# TurboMaster-clean_noart.net
KiCad netlist of a schematic drawn in EAGLE
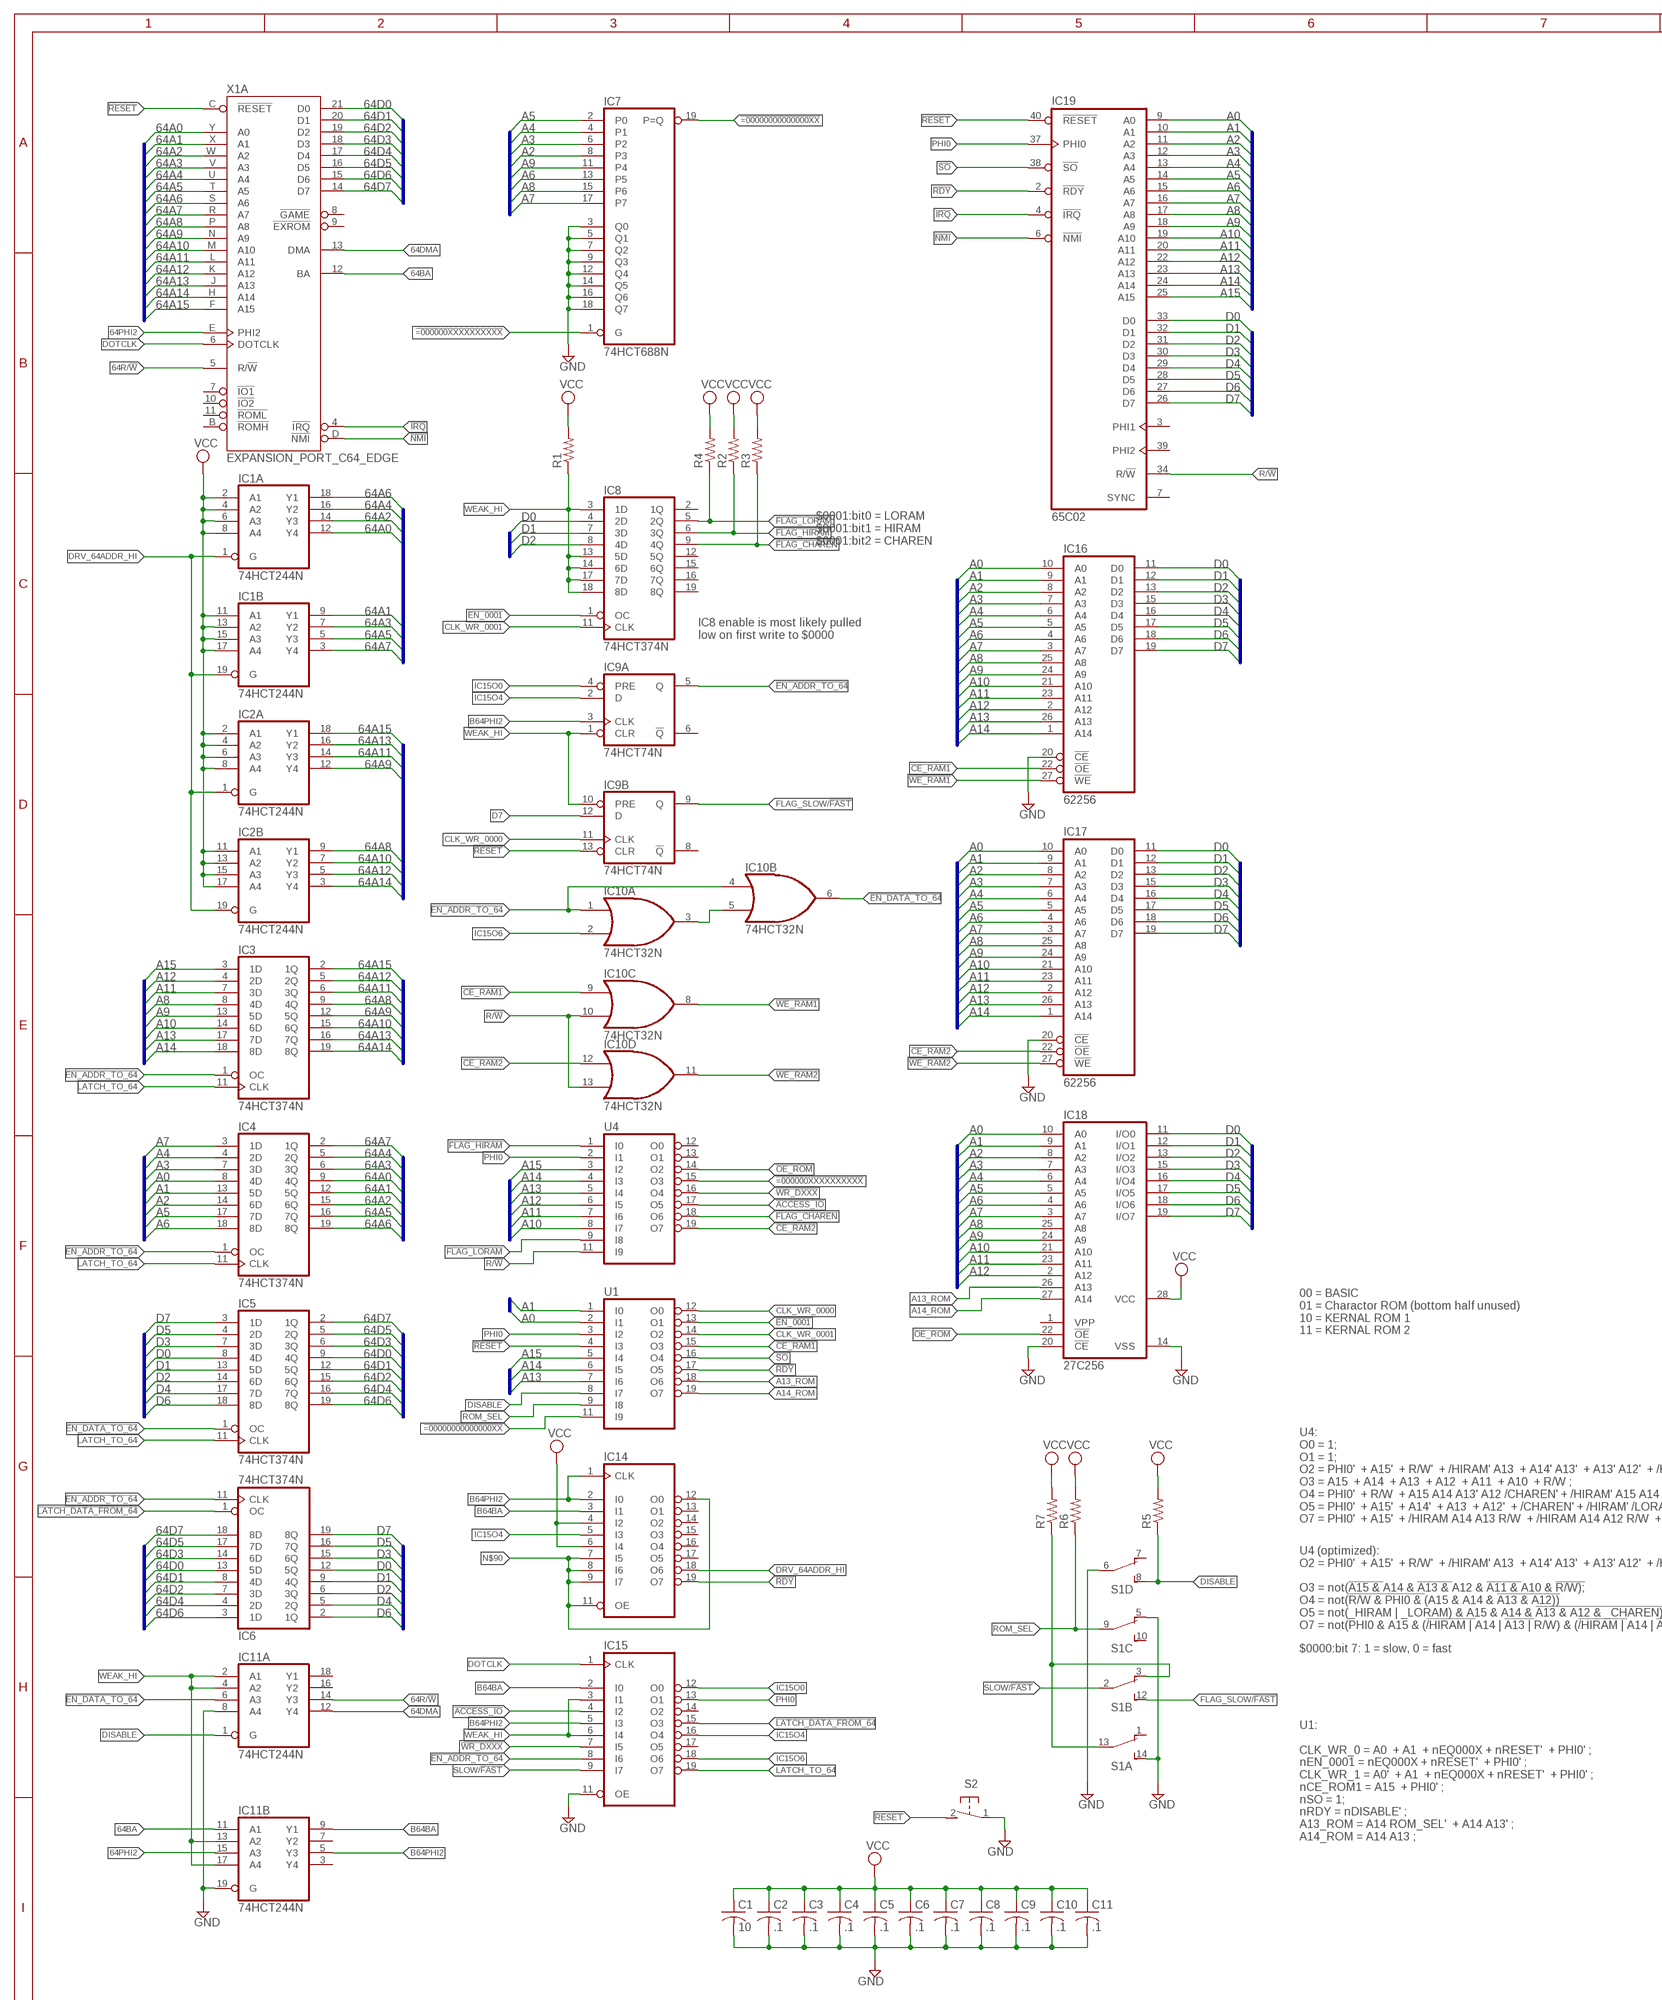
[diagram p0: schematic, sheet 1, part 1 of 2]
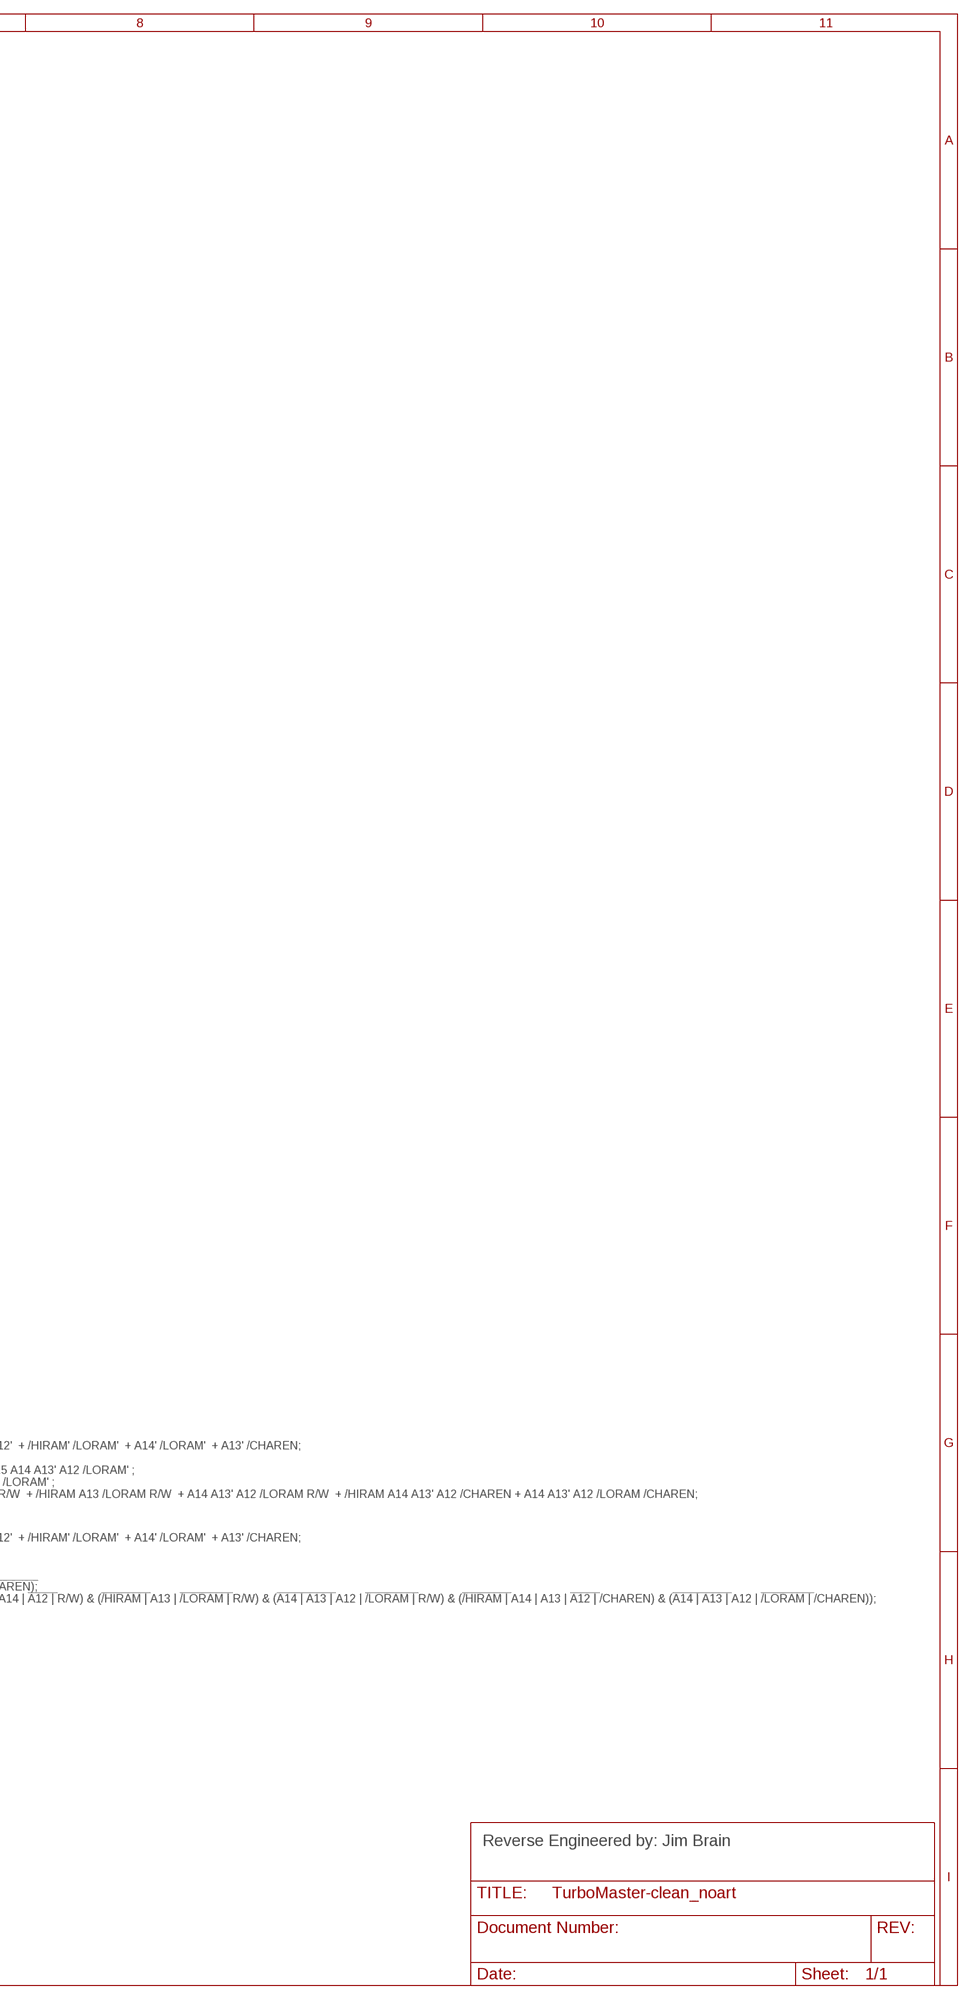
[diagram p1: schematic, sheet 1, part 2 of 2]

(export (version "E")
  (design (tool "Eeschema 10.0.6"))
  (components
    (comp (ref "C1")
      (value "10")
      (footprint "eagle-import:C050-024X044")
      (libsource (lib "eagle-import") (part "C-US050-024X044"))
    )
    (comp (ref "C2")
      (value ".1")
      (footprint "eagle-import:C050-024X044")
      (libsource (lib "eagle-import") (part "C-US050-024X044"))
    )
    (comp (ref "C3")
      (value ".1")
      (footprint "eagle-import:C050-024X044")
      (libsource (lib "eagle-import") (part "C-US050-024X044"))
    )
    (comp (ref "C4")
      (value ".1")
      (footprint "eagle-import:C050-024X044")
      (libsource (lib "eagle-import") (part "C-US050-024X044"))
    )
    (comp (ref "C5")
      (value ".1")
      (footprint "eagle-import:C050-024X044")
      (libsource (lib "eagle-import") (part "C-US050-024X044"))
    )
    (comp (ref "C6")
      (value ".1")
      (footprint "eagle-import:C050-024X044")
      (libsource (lib "eagle-import") (part "C-US050-024X044"))
    )
    (comp (ref "C7")
      (value ".1")
      (footprint "eagle-import:C050-024X044")
      (libsource (lib "eagle-import") (part "C-US050-024X044"))
    )
    (comp (ref "C8")
      (value ".1")
      (footprint "eagle-import:C050-024X044")
      (libsource (lib "eagle-import") (part "C-US050-024X044"))
    )
    (comp (ref "C9")
      (value ".1")
      (footprint "eagle-import:C050-024X044")
      (libsource (lib "eagle-import") (part "C-US050-024X044"))
    )
    (comp (ref "C10")
      (value ".1")
      (footprint "eagle-import:C050-024X044")
      (libsource (lib "eagle-import") (part "C-US050-024X044"))
    )
    (comp (ref "C11")
      (value ".1")
      (footprint "eagle-import:C050-024X044")
      (libsource (lib "eagle-import") (part "C-US050-024X044"))
    )
    (comp (ref "IC1")
      (value "74HCT244N")
      (footprint "eagle-import:DIL20-RP")
      (libsource (lib "eagle-import") (part "74244NHCT"))
    )
    (comp (ref "IC2")
      (value "74HCT244N")
      (footprint "eagle-import:DIL20-RP")
      (libsource (lib "eagle-import") (part "74244NHCT"))
    )
    (comp (ref "IC3")
      (value "74HCT374N")
      (footprint "eagle-import:DIL20-RP")
      (libsource (lib "eagle-import") (part "74374NHCT"))
    )
    (comp (ref "IC4")
      (value "74HCT374N")
      (footprint "eagle-import:DIL20-RP")
      (libsource (lib "eagle-import") (part "74374NHCT"))
    )
    (comp (ref "IC5")
      (value "74HCT374N")
      (footprint "eagle-import:DIL20-RP")
      (libsource (lib "eagle-import") (part "74374NHCT"))
    )
    (comp (ref "IC6")
      (value "74HCT374N")
      (footprint "eagle-import:DIL20-RP")
      (libsource (lib "eagle-import") (part "74374NHCT"))
    )
    (comp (ref "IC7")
      (value "74HCT688N")
      (footprint "eagle-import:DIL20-RP")
      (libsource (lib "eagle-import") (part "74688NHCT"))
    )
    (comp (ref "IC8")
      (value "74HCT374N")
      (footprint "eagle-import:DIL20-RP")
      (libsource (lib "eagle-import") (part "74374NHCT"))
    )
    (comp (ref "IC9")
      (value "74HCT74N")
      (footprint "eagle-import:DIL14-RP")
      (libsource (lib "eagle-import") (part "7474NHCT"))
    )
    (comp (ref "IC10")
      (value "74HCT32N")
      (footprint "eagle-import:DIL14-RP")
      (libsource (lib "eagle-import") (part "7432NHCT"))
    )
    (comp (ref "IC11")
      (value "74HCT244N")
      (footprint "eagle-import:DIL20-RP")
      (libsource (lib "eagle-import") (part "74244NHCT"))
    )
    (comp (ref "IC14")
      (value "16R4-RP")
      (footprint "eagle-import:DIL20-RP")
      (libsource (lib "eagle-import") (part "16R4-RP"))
    )
    (comp (ref "IC15")
      (value "16R6-RP")
      (footprint "eagle-import:DIL20-RP")
      (libsource (lib "eagle-import") (part "16R6-RP"))
    )
    (comp (ref "IC16")
      (value "62256")
      (footprint "eagle-import:DIL28-6-RP")
      (libsource (lib "eagle-import") (part "JEDEC_32KB_SRAM-RP"))
    )
    (comp (ref "IC17")
      (value "62256")
      (footprint "eagle-import:DIL28-6-RP")
      (libsource (lib "eagle-import") (part "JEDEC_32KB_SRAM-RP"))
    )
    (comp (ref "IC18")
      (value "27C256")
      (footprint "eagle-import:DIL28-6-RP")
      (libsource (lib "eagle-import") (part "27C256AG-RP"))
    )
    (comp (ref "IC19")
      (value "65C02")
      (footprint "eagle-import:DIL40-ROUNDPAD")
      (libsource (lib "eagle-import") (part "6502-RPC"))
    )
    (comp (ref "R1")
      (value "R-US_0207/10")
      (footprint "eagle-import:0207_10")
      (libsource (lib "eagle-import") (part "R-US_0207/10"))
    )
    (comp (ref "R2")
      (value "R-US_0207/10")
      (footprint "eagle-import:0207_10")
      (libsource (lib "eagle-import") (part "R-US_0207/10"))
    )
    (comp (ref "R3")
      (value "R-US_0207/10")
      (footprint "eagle-import:0207_10")
      (libsource (lib "eagle-import") (part "R-US_0207/10"))
    )
    (comp (ref "R4")
      (value "R-US_0207/10")
      (footprint "eagle-import:0207_10")
      (libsource (lib "eagle-import") (part "R-US_0207/10"))
    )
    (comp (ref "R5")
      (value "R-US_0207/10")
      (footprint "eagle-import:0207_10")
      (libsource (lib "eagle-import") (part "R-US_0207/10"))
    )
    (comp (ref "R6")
      (value "R-US_0207/10")
      (footprint "eagle-import:0207_10")
      (libsource (lib "eagle-import") (part "R-US_0207/10"))
    )
    (comp (ref "R7")
      (value "R-US_0207/10")
      (footprint "eagle-import:0207_10")
      (libsource (lib "eagle-import") (part "R-US_0207/10"))
    )
    (comp (ref "S1")
      (value "DIP04DPDTS-RP")
      (footprint "eagle-import:DIP04DPDTS-RP")
      (libsource (lib "eagle-import") (part "DIP04DPDTS-RP"))
    )
    (comp (ref "S2")
      (value "31-XX")
      (footprint "eagle-import:B3F-31XX")
      (fields (field (name "MPN") "B3F-3100"))
      (libsource (lib "eagle-import") (part "31-XX"))
    )
    (comp (ref "U1")
      (value "16L8-RP")
      (footprint "eagle-import:DIL20-RP")
      (libsource (lib "eagle-import") (part "16L8-RP"))
    )
    (comp (ref "U4")
      (value "16L8-RP")
      (footprint "eagle-import:DIL20-RP")
      (libsource (lib "eagle-import") (part "16L8-RP"))
    )
    (comp (ref "X1")
      (value "EXPANSION_PORT_C64_EDGE")
      (footprint "eagle-import:MA100-22-2")
      (libsource (lib "eagle-import") (part "EXPANSION_PORT_C64_EDGE"))
    )
  )
  (nets
    (net (code "1") (name "/64A0") (class "Default")
      (node (ref "IC1") (pin "12") (pinfunction "Y4_12") (pintype "tri_state"))
      (node (ref "IC4") (pin "9") (pinfunction "4Q_9") (pintype "tri_state"))
      (node (ref "X1") (pin "Y") (pinfunction "A0_Y") (pintype "bidirectional"))
    )
    (net (code "2") (name "/64A1") (class "Default")
      (node (ref "IC1") (pin "9") (pinfunction "Y1_9") (pintype "tri_state"))
      (node (ref "IC4") (pin "12") (pinfunction "5Q_12") (pintype "tri_state"))
      (node (ref "X1") (pin "X") (pinfunction "A1_X") (pintype "bidirectional"))
    )
    (net (code "3") (name "/64A2") (class "Default")
      (node (ref "IC1") (pin "14") (pinfunction "Y3_14") (pintype "tri_state"))
      (node (ref "IC4") (pin "15") (pinfunction "6Q_15") (pintype "tri_state"))
      (node (ref "X1") (pin "W") (pinfunction "A2_W") (pintype "bidirectional"))
    )
    (net (code "4") (name "/64A3") (class "Default")
      (node (ref "IC1") (pin "7") (pinfunction "Y2_7") (pintype "tri_state"))
      (node (ref "IC4") (pin "6") (pinfunction "3Q_6") (pintype "tri_state"))
      (node (ref "X1") (pin "V") (pinfunction "A3_V") (pintype "bidirectional"))
    )
    (net (code "5") (name "/64A4") (class "Default")
      (node (ref "IC1") (pin "16") (pinfunction "Y2_16") (pintype "tri_state"))
      (node (ref "IC4") (pin "5") (pinfunction "2Q_5") (pintype "tri_state"))
      (node (ref "X1") (pin "U") (pinfunction "A4_U") (pintype "bidirectional"))
    )
    (net (code "6") (name "/64A5") (class "Default")
      (node (ref "IC1") (pin "5") (pinfunction "Y3_5") (pintype "tri_state"))
      (node (ref "IC4") (pin "16") (pinfunction "7Q_16") (pintype "tri_state"))
      (node (ref "X1") (pin "T") (pinfunction "A5_T") (pintype "bidirectional"))
    )
    (net (code "7") (name "/64A6") (class "Default")
      (node (ref "IC1") (pin "18") (pinfunction "Y1_18") (pintype "tri_state"))
      (node (ref "IC4") (pin "19") (pinfunction "8Q_19") (pintype "tri_state"))
      (node (ref "X1") (pin "S") (pinfunction "A6_S") (pintype "bidirectional"))
    )
    (net (code "8") (name "/64A7") (class "Default")
      (node (ref "IC1") (pin "3") (pinfunction "Y4_3") (pintype "tri_state"))
      (node (ref "IC4") (pin "2") (pinfunction "1Q_2") (pintype "tri_state"))
      (node (ref "X1") (pin "R") (pinfunction "A7_R") (pintype "bidirectional"))
    )
    (net (code "9") (name "/64A8") (class "Default")
      (node (ref "IC2") (pin "9") (pinfunction "Y1_9") (pintype "tri_state"))
      (node (ref "IC3") (pin "9") (pinfunction "4Q_9") (pintype "tri_state"))
      (node (ref "X1") (pin "P") (pinfunction "A8_P") (pintype "bidirectional"))
    )
    (net (code "10") (name "/64A9") (class "Default")
      (node (ref "IC2") (pin "12") (pinfunction "Y4_12") (pintype "tri_state"))
      (node (ref "IC3") (pin "12") (pinfunction "5Q_12") (pintype "tri_state"))
      (node (ref "X1") (pin "N") (pinfunction "A9_N") (pintype "bidirectional"))
    )
    (net (code "11") (name "/64A10") (class "Default")
      (node (ref "IC2") (pin "7") (pinfunction "Y2_7") (pintype "tri_state"))
      (node (ref "IC3") (pin "15") (pinfunction "6Q_15") (pintype "tri_state"))
      (node (ref "X1") (pin "M") (pinfunction "A10_M") (pintype "bidirectional"))
    )
    (net (code "12") (name "/64A11") (class "Default")
      (node (ref "IC2") (pin "14") (pinfunction "Y3_14") (pintype "tri_state"))
      (node (ref "IC3") (pin "6") (pinfunction "3Q_6") (pintype "tri_state"))
      (node (ref "X1") (pin "L") (pinfunction "A11_L") (pintype "bidirectional"))
    )
    (net (code "13") (name "/64A12") (class "Default")
      (node (ref "IC2") (pin "5") (pinfunction "Y3_5") (pintype "tri_state"))
      (node (ref "IC3") (pin "5") (pinfunction "2Q_5") (pintype "tri_state"))
      (node (ref "X1") (pin "K") (pinfunction "A12_K") (pintype "bidirectional"))
    )
    (net (code "14") (name "/64A13") (class "Default")
      (node (ref "IC2") (pin "16") (pinfunction "Y2_16") (pintype "tri_state"))
      (node (ref "IC3") (pin "16") (pinfunction "7Q_16") (pintype "tri_state"))
      (node (ref "X1") (pin "J") (pinfunction "A13_J") (pintype "bidirectional"))
    )
    (net (code "15") (name "/64A14") (class "Default")
      (node (ref "IC2") (pin "3") (pinfunction "Y4_3") (pintype "tri_state"))
      (node (ref "IC3") (pin "19") (pinfunction "8Q_19") (pintype "tri_state"))
      (node (ref "X1") (pin "H") (pinfunction "A14_H") (pintype "bidirectional"))
    )
    (net (code "16") (name "/64A15") (class "Default")
      (node (ref "IC2") (pin "18") (pinfunction "Y1_18") (pintype "tri_state"))
      (node (ref "IC3") (pin "2") (pinfunction "1Q_2") (pintype "tri_state"))
      (node (ref "X1") (pin "F") (pinfunction "A15_F") (pintype "bidirectional"))
    )
    (net (code "17") (name "/64D0") (class "Default")
      (node (ref "IC5") (pin "9") (pinfunction "4Q_9") (pintype "tri_state"))
      (node (ref "IC6") (pin "13") (pinfunction "5D_13") (pintype "input"))
      (node (ref "X1") (pin "21") (pinfunction "D0_21") (pintype "bidirectional"))
    )
    (net (code "18") (name "/64D1") (class "Default")
      (node (ref "IC5") (pin "12") (pinfunction "5Q_12") (pintype "tri_state"))
      (node (ref "IC6") (pin "8") (pinfunction "4D_8") (pintype "input"))
      (node (ref "X1") (pin "20") (pinfunction "D1_20") (pintype "bidirectional"))
    )
    (net (code "19") (name "/64D2") (class "Default")
      (node (ref "IC5") (pin "15") (pinfunction "6Q_15") (pintype "tri_state"))
      (node (ref "IC6") (pin "7") (pinfunction "3D_7") (pintype "input"))
      (node (ref "X1") (pin "19") (pinfunction "D2_19") (pintype "bidirectional"))
    )
    (net (code "20") (name "/64D3") (class "Default")
      (node (ref "IC5") (pin "6") (pinfunction "3Q_6") (pintype "tri_state"))
      (node (ref "IC6") (pin "14") (pinfunction "6D_14") (pintype "input"))
      (node (ref "X1") (pin "18") (pinfunction "D3_18") (pintype "bidirectional"))
    )
    (net (code "21") (name "/64D4") (class "Default")
      (node (ref "IC5") (pin "16") (pinfunction "7Q_16") (pintype "tri_state"))
      (node (ref "IC6") (pin "4") (pinfunction "2D_4") (pintype "input"))
      (node (ref "X1") (pin "17") (pinfunction "D4_17") (pintype "bidirectional"))
    )
    (net (code "22") (name "/64D5") (class "Default")
      (node (ref "IC5") (pin "5") (pinfunction "2Q_5") (pintype "tri_state"))
      (node (ref "IC6") (pin "17") (pinfunction "7D_17") (pintype "input"))
      (node (ref "X1") (pin "16") (pinfunction "D5_16") (pintype "bidirectional"))
    )
    (net (code "23") (name "/64D6") (class "Default")
      (node (ref "IC5") (pin "19") (pinfunction "8Q_19") (pintype "tri_state"))
      (node (ref "IC6") (pin "3") (pinfunction "1D_3") (pintype "input"))
      (node (ref "X1") (pin "15") (pinfunction "D6_15") (pintype "bidirectional"))
    )
    (net (code "24") (name "/64D7") (class "Default")
      (node (ref "IC5") (pin "2") (pinfunction "1Q_2") (pintype "tri_state"))
      (node (ref "IC6") (pin "18") (pinfunction "8D_18") (pintype "input"))
      (node (ref "X1") (pin "14") (pinfunction "D7_14") (pintype "bidirectional"))
    )
    (net (code "25") (name "/64R{slash}~{W}") (class "Default")
      (node (ref "IC11") (pin "14") (pinfunction "Y3_14") (pintype "tri_state"))
      (node (ref "X1") (pin "5") (pinfunction "R/~{W}_5") (pintype "bidirectional"))
    )
    (net (code "26") (name "/A0") (class "Default")
      (node (ref "IC16") (pin "10") (pinfunction "A0_10") (pintype "input"))
      (node (ref "IC17") (pin "10") (pinfunction "A0_10") (pintype "input"))
      (node (ref "IC18") (pin "10") (pinfunction "A0_10") (pintype "input"))
      (node (ref "IC19") (pin "9") (pinfunction "A0_9") (pintype "output"))
      (node (ref "IC4") (pin "8") (pinfunction "4D_8") (pintype "input"))
      (node (ref "U1") (pin "2") (pinfunction "I1_2") (pintype "input"))
    )
    (net (code "27") (name "/A1") (class "Default")
      (node (ref "IC16") (pin "9") (pinfunction "A1_9") (pintype "input"))
      (node (ref "IC17") (pin "9") (pinfunction "A1_9") (pintype "input"))
      (node (ref "IC18") (pin "9") (pinfunction "A1_9") (pintype "input"))
      (node (ref "IC19") (pin "10") (pinfunction "A1_10") (pintype "output"))
      (node (ref "IC4") (pin "13") (pinfunction "5D_13") (pintype "input"))
      (node (ref "U1") (pin "1") (pinfunction "I0_1") (pintype "input"))
    )
    (net (code "28") (name "/A2") (class "Default")
      (node (ref "IC16") (pin "8") (pinfunction "A2_8") (pintype "input"))
      (node (ref "IC17") (pin "8") (pinfunction "A2_8") (pintype "input"))
      (node (ref "IC18") (pin "8") (pinfunction "A2_8") (pintype "input"))
      (node (ref "IC19") (pin "11") (pinfunction "A2_11") (pintype "output"))
      (node (ref "IC4") (pin "14") (pinfunction "6D_14") (pintype "input"))
      (node (ref "IC7") (pin "8") (pinfunction "P3_8") (pintype "input"))
    )
    (net (code "29") (name "/A3") (class "Default")
      (node (ref "IC16") (pin "7") (pinfunction "A3_7") (pintype "input"))
      (node (ref "IC17") (pin "7") (pinfunction "A3_7") (pintype "input"))
      (node (ref "IC18") (pin "7") (pinfunction "A3_7") (pintype "input"))
      (node (ref "IC19") (pin "12") (pinfunction "A3_12") (pintype "output"))
      (node (ref "IC4") (pin "7") (pinfunction "3D_7") (pintype "input"))
      (node (ref "IC7") (pin "6") (pinfunction "P2_6") (pintype "input"))
    )
    (net (code "30") (name "/A4") (class "Default")
      (node (ref "IC16") (pin "6") (pinfunction "A4_6") (pintype "input"))
      (node (ref "IC17") (pin "6") (pinfunction "A4_6") (pintype "input"))
      (node (ref "IC18") (pin "6") (pinfunction "A4_6") (pintype "input"))
      (node (ref "IC19") (pin "13") (pinfunction "A4_13") (pintype "output"))
      (node (ref "IC4") (pin "4") (pinfunction "2D_4") (pintype "input"))
      (node (ref "IC7") (pin "4") (pinfunction "P1_4") (pintype "input"))
    )
    (net (code "31") (name "/A5") (class "Default")
      (node (ref "IC16") (pin "5") (pinfunction "A5_5") (pintype "input"))
      (node (ref "IC17") (pin "5") (pinfunction "A5_5") (pintype "input"))
      (node (ref "IC18") (pin "5") (pinfunction "A5_5") (pintype "input"))
      (node (ref "IC19") (pin "14") (pinfunction "A5_14") (pintype "output"))
      (node (ref "IC4") (pin "17") (pinfunction "7D_17") (pintype "input"))
      (node (ref "IC7") (pin "2") (pinfunction "P0_2") (pintype "input"))
    )
    (net (code "32") (name "/A6") (class "Default")
      (node (ref "IC16") (pin "4") (pinfunction "A6_4") (pintype "input"))
      (node (ref "IC17") (pin "4") (pinfunction "A6_4") (pintype "input"))
      (node (ref "IC18") (pin "4") (pinfunction "A6_4") (pintype "input"))
      (node (ref "IC19") (pin "15") (pinfunction "A6_15") (pintype "output"))
      (node (ref "IC4") (pin "18") (pinfunction "8D_18") (pintype "input"))
      (node (ref "IC7") (pin "13") (pinfunction "P5_13") (pintype "input"))
    )
    (net (code "33") (name "/A7") (class "Default")
      (node (ref "IC16") (pin "3") (pinfunction "A7_3") (pintype "input"))
      (node (ref "IC17") (pin "3") (pinfunction "A7_3") (pintype "input"))
      (node (ref "IC18") (pin "3") (pinfunction "A7_3") (pintype "input"))
      (node (ref "IC19") (pin "16") (pinfunction "A7_16") (pintype "output"))
      (node (ref "IC4") (pin "3") (pinfunction "1D_3") (pintype "input"))
      (node (ref "IC7") (pin "17") (pinfunction "P7_17") (pintype "input"))
    )
    (net (code "34") (name "/A8") (class "Default")
      (node (ref "IC16") (pin "25") (pinfunction "A8_25") (pintype "input"))
      (node (ref "IC17") (pin "25") (pinfunction "A8_25") (pintype "input"))
      (node (ref "IC18") (pin "25") (pinfunction "A8_25") (pintype "input"))
      (node (ref "IC19") (pin "17") (pinfunction "A8_17") (pintype "output"))
      (node (ref "IC3") (pin "8") (pinfunction "4D_8") (pintype "input"))
      (node (ref "IC7") (pin "15") (pinfunction "P6_15") (pintype "input"))
    )
    (net (code "35") (name "/A9") (class "Default")
      (node (ref "IC16") (pin "24") (pinfunction "A9_24") (pintype "input"))
      (node (ref "IC17") (pin "24") (pinfunction "A9_24") (pintype "input"))
      (node (ref "IC18") (pin "24") (pinfunction "A9_24") (pintype "input"))
      (node (ref "IC19") (pin "18") (pinfunction "A9_18") (pintype "output"))
      (node (ref "IC3") (pin "13") (pinfunction "5D_13") (pintype "input"))
      (node (ref "IC7") (pin "11") (pinfunction "P4_11") (pintype "input"))
    )
    (net (code "36") (name "/A10") (class "Default")
      (node (ref "IC16") (pin "21") (pinfunction "A10_21") (pintype "input"))
      (node (ref "IC17") (pin "21") (pinfunction "A10_21") (pintype "input"))
      (node (ref "IC18") (pin "21") (pinfunction "A10_21") (pintype "input"))
      (node (ref "IC19") (pin "19") (pinfunction "A10_19") (pintype "output"))
      (node (ref "IC3") (pin "14") (pinfunction "6D_14") (pintype "input"))
      (node (ref "U4") (pin "8") (pinfunction "I7_8") (pintype "input"))
    )
    (net (code "37") (name "/A11") (class "Default")
      (node (ref "IC16") (pin "23") (pinfunction "A11_23") (pintype "input"))
      (node (ref "IC17") (pin "23") (pinfunction "A11_23") (pintype "input"))
      (node (ref "IC18") (pin "23") (pinfunction "A11_23") (pintype "input"))
      (node (ref "IC19") (pin "20") (pinfunction "A11_20") (pintype "output"))
      (node (ref "IC3") (pin "7") (pinfunction "3D_7") (pintype "input"))
      (node (ref "U4") (pin "7") (pinfunction "I6_7") (pintype "input"))
    )
    (net (code "38") (name "/A12") (class "Default")
      (node (ref "IC16") (pin "2") (pinfunction "A12_2") (pintype "input"))
      (node (ref "IC17") (pin "2") (pinfunction "A12_2") (pintype "input"))
      (node (ref "IC18") (pin "2") (pinfunction "A12_2") (pintype "input"))
      (node (ref "IC19") (pin "22") (pinfunction "A12_22") (pintype "output"))
      (node (ref "IC3") (pin "4") (pinfunction "2D_4") (pintype "input"))
      (node (ref "U4") (pin "6") (pinfunction "I5_6") (pintype "input"))
    )
    (net (code "39") (name "/A13") (class "Default")
      (node (ref "IC16") (pin "26") (pinfunction "A13_26") (pintype "input"))
      (node (ref "IC17") (pin "26") (pinfunction "A13_26") (pintype "input"))
      (node (ref "IC19") (pin "23") (pinfunction "A13_23") (pintype "output"))
      (node (ref "IC3") (pin "17") (pinfunction "7D_17") (pintype "input"))
      (node (ref "U1") (pin "7") (pinfunction "I6_7") (pintype "input"))
      (node (ref "U4") (pin "5") (pinfunction "I4_5") (pintype "input"))
    )
    (net (code "40") (name "/A14") (class "Default")
      (node (ref "IC16") (pin "1") (pinfunction "A14_1") (pintype "input"))
      (node (ref "IC17") (pin "1") (pinfunction "A14_1") (pintype "input"))
      (node (ref "IC19") (pin "24") (pinfunction "A14_24") (pintype "output"))
      (node (ref "IC3") (pin "18") (pinfunction "8D_18") (pintype "input"))
      (node (ref "U1") (pin "6") (pinfunction "I5_6") (pintype "input"))
      (node (ref "U4") (pin "4") (pinfunction "I3_4") (pintype "input"))
    )
    (net (code "41") (name "/A15") (class "Default")
      (node (ref "IC19") (pin "25") (pinfunction "A15_25") (pintype "output"))
      (node (ref "IC3") (pin "3") (pinfunction "1D_3") (pintype "input"))
      (node (ref "U1") (pin "5") (pinfunction "I4_5") (pintype "input"))
      (node (ref "U4") (pin "3") (pinfunction "I2_3") (pintype "input"))
    )
    (net (code "42") (name "/D0") (class "Default")
      (node (ref "IC16") (pin "11") (pinfunction "D0_11") (pintype "bidirectional"))
      (node (ref "IC17") (pin "11") (pinfunction "D0_11") (pintype "bidirectional"))
      (node (ref "IC18") (pin "11") (pinfunction "I/O0_11") (pintype "tri_state"))
      (node (ref "IC19") (pin "33") (pinfunction "D0_33") (pintype "bidirectional"))
      (node (ref "IC5") (pin "8") (pinfunction "4D_8") (pintype "input"))
      (node (ref "IC6") (pin "12") (pinfunction "5Q_12") (pintype "tri_state"))
      (node (ref "IC8") (pin "4") (pinfunction "2D_4") (pintype "input"))
    )
    (net (code "43") (name "/D1") (class "Default")
      (node (ref "IC16") (pin "12") (pinfunction "D1_12") (pintype "bidirectional"))
      (node (ref "IC17") (pin "12") (pinfunction "D1_12") (pintype "bidirectional"))
      (node (ref "IC18") (pin "12") (pinfunction "I/O1_12") (pintype "tri_state"))
      (node (ref "IC19") (pin "32") (pinfunction "D1_32") (pintype "bidirectional"))
      (node (ref "IC5") (pin "13") (pinfunction "5D_13") (pintype "input"))
      (node (ref "IC6") (pin "9") (pinfunction "4Q_9") (pintype "tri_state"))
      (node (ref "IC8") (pin "7") (pinfunction "3D_7") (pintype "input"))
    )
    (net (code "44") (name "/D2") (class "Default")
      (node (ref "IC16") (pin "13") (pinfunction "D2_13") (pintype "bidirectional"))
      (node (ref "IC17") (pin "13") (pinfunction "D2_13") (pintype "bidirectional"))
      (node (ref "IC18") (pin "13") (pinfunction "I/O2_13") (pintype "tri_state"))
      (node (ref "IC19") (pin "31") (pinfunction "D2_31") (pintype "bidirectional"))
      (node (ref "IC5") (pin "14") (pinfunction "6D_14") (pintype "input"))
      (node (ref "IC6") (pin "6") (pinfunction "3Q_6") (pintype "tri_state"))
      (node (ref "IC8") (pin "8") (pinfunction "4D_8") (pintype "input"))
    )
    (net (code "45") (name "/D3") (class "Default")
      (node (ref "IC16") (pin "15") (pinfunction "D3_15") (pintype "bidirectional"))
      (node (ref "IC17") (pin "15") (pinfunction "D3_15") (pintype "bidirectional"))
      (node (ref "IC18") (pin "15") (pinfunction "I/O3_15") (pintype "tri_state"))
      (node (ref "IC19") (pin "30") (pinfunction "D3_30") (pintype "bidirectional"))
      (node (ref "IC5") (pin "7") (pinfunction "3D_7") (pintype "input"))
      (node (ref "IC6") (pin "15") (pinfunction "6Q_15") (pintype "tri_state"))
    )
    (net (code "46") (name "/D4") (class "Default")
      (node (ref "IC16") (pin "16") (pinfunction "D4_16") (pintype "bidirectional"))
      (node (ref "IC17") (pin "16") (pinfunction "D4_16") (pintype "bidirectional"))
      (node (ref "IC18") (pin "16") (pinfunction "I/O4_16") (pintype "tri_state"))
      (node (ref "IC19") (pin "29") (pinfunction "D4_29") (pintype "bidirectional"))
      (node (ref "IC5") (pin "17") (pinfunction "7D_17") (pintype "input"))
      (node (ref "IC6") (pin "5") (pinfunction "2Q_5") (pintype "tri_state"))
    )
    (net (code "47") (name "/D5") (class "Default")
      (node (ref "IC16") (pin "17") (pinfunction "D5_17") (pintype "bidirectional"))
      (node (ref "IC17") (pin "17") (pinfunction "D5_17") (pintype "bidirectional"))
      (node (ref "IC18") (pin "17") (pinfunction "I/O5_17") (pintype "tri_state"))
      (node (ref "IC19") (pin "28") (pinfunction "D5_28") (pintype "bidirectional"))
      (node (ref "IC5") (pin "4") (pinfunction "2D_4") (pintype "input"))
      (node (ref "IC6") (pin "16") (pinfunction "7Q_16") (pintype "tri_state"))
    )
    (net (code "48") (name "/D6") (class "Default")
      (node (ref "IC16") (pin "18") (pinfunction "D6_18") (pintype "bidirectional"))
      (node (ref "IC17") (pin "18") (pinfunction "D6_18") (pintype "bidirectional"))
      (node (ref "IC18") (pin "18") (pinfunction "I/O6_18") (pintype "tri_state"))
      (node (ref "IC19") (pin "27") (pinfunction "D6_27") (pintype "bidirectional"))
      (node (ref "IC5") (pin "18") (pinfunction "8D_18") (pintype "input"))
      (node (ref "IC6") (pin "2") (pinfunction "1Q_2") (pintype "tri_state"))
    )
    (net (code "49") (name "/FLAG_SLOW{slash}~{FAST}") (class "Default")
      (node (ref "IC9") (pin "9") (pinfunction "Q_9") (pintype "output"))
      (node (ref "S1") (pin "12") (pinfunction "S_12") (pintype "passive"))
    )
    (net (code "50") (name "/R{slash}~{W}") (class "Default")
      (node (ref "IC10") (pin "10") (pinfunction "I1_10") (pintype "input"))
      (node (ref "IC10") (pin "13") (pinfunction "I1_13") (pintype "input"))
      (node (ref "IC19") (pin "34") (pinfunction "R/~{W}_34") (pintype "output"))
      (node (ref "U4") (pin "11") (pinfunction "I9_11") (pintype "input"))
    )
    (net (code "51") (name "/SLOW{slash}~{FAST}") (class "Default")
      (node (ref "IC15") (pin "9") (pinfunction "I7_9") (pintype "input"))
      (node (ref "S1") (pin "2") (pinfunction "P_2") (pintype "passive"))
    )
    (net (code "52") (name "/~{=000000XXXXXXXXXX}") (class "Default")
      (node (ref "IC7") (pin "1") (pinfunction "G_1") (pintype "input"))
      (node (ref "U4") (pin "15") (pinfunction "O3_15") (pintype "bidirectional"))
    )
    (net (code "53") (name "/~{=00000000000000XX}") (class "Default")
      (node (ref "IC7") (pin "19") (pinfunction "P=Q_19") (pintype "output"))
      (node (ref "U1") (pin "11") (pinfunction "I9_11") (pintype "input"))
    )
    (net (code "54") (name "/~{ACCESS_IO}") (class "Default")
      (node (ref "IC15") (pin "4") (pinfunction "I2_4") (pintype "input"))
      (node (ref "U4") (pin "17") (pinfunction "O5_17") (pintype "bidirectional"))
    )
    (net (code "55") (name "/~{CE_RAM1}") (class "Default")
      (node (ref "IC10") (pin "9") (pinfunction "I0_9") (pintype "input"))
      (node (ref "IC16") (pin "22") (pinfunction "~{OE}_22") (pintype "input"))
      (node (ref "U1") (pin "15") (pinfunction "O3_15") (pintype "bidirectional"))
    )
    (net (code "56") (name "/~{CE_RAM2}") (class "Default")
      (node (ref "IC10") (pin "12") (pinfunction "I0_12") (pintype "input"))
      (node (ref "IC17") (pin "22") (pinfunction "~{OE}_22") (pintype "input"))
      (node (ref "U4") (pin "19") (pinfunction "O7_19") (pintype "output"))
    )
    (net (code "57") (name "/~{EN_0001}") (class "Default")
      (node (ref "IC8") (pin "1") (pinfunction "OC_1") (pintype "input"))
      (node (ref "U1") (pin "13") (pinfunction "O1_13") (pintype "bidirectional"))
    )
    (net (code "58") (name "/~{EN_ADDR_TO_64}") (class "Default")
      (node (ref "IC10") (pin "1") (pinfunction "I0_1") (pintype "input"))
      (node (ref "IC10") (pin "4") (pinfunction "I0_4") (pintype "input"))
      (node (ref "IC15") (pin "8") (pinfunction "I6_8") (pintype "input"))
      (node (ref "IC3") (pin "1") (pinfunction "OC_1") (pintype "input"))
      (node (ref "IC4") (pin "1") (pinfunction "OC_1") (pintype "input"))
      (node (ref "IC6") (pin "11") (pinfunction "CLK_11") (pintype "input"))
      (node (ref "IC9") (pin "5") (pinfunction "Q_5") (pintype "output"))
    )
    (net (code "59") (name "/~{EN_DATA_TO_64}") (class "Default")
      (node (ref "IC10") (pin "6") (pinfunction "O_6") (pintype "output"))
      (node (ref "IC11") (pin "6") (pinfunction "A3_6") (pintype "input"))
      (node (ref "IC5") (pin "1") (pinfunction "OC_1") (pintype "input"))
    )
    (net (code "60") (name "/~{FLAG_CHAREN}") (class "Default")
      (node (ref "IC8") (pin "9") (pinfunction "4Q_9") (pintype "tri_state"))
      (node (ref "R3") (pin "1") (pinfunction "1_1") (pintype "passive"))
      (node (ref "U4") (pin "18") (pinfunction "O6_18") (pintype "bidirectional"))
    )
    (net (code "61") (name "/~{FLAG_HIRAM}") (class "Default")
      (node (ref "IC8") (pin "6") (pinfunction "3Q_6") (pintype "tri_state"))
      (node (ref "R2") (pin "1") (pinfunction "1_1") (pintype "passive"))
      (node (ref "U4") (pin "1") (pinfunction "I0_1") (pintype "input"))
    )
    (net (code "62") (name "/~{FLAG_LORAM}") (class "Default")
      (node (ref "IC8") (pin "5") (pinfunction "2Q_5") (pintype "tri_state"))
      (node (ref "R4") (pin "1") (pinfunction "1_1") (pintype "passive"))
      (node (ref "U4") (pin "9") (pinfunction "I8_9") (pintype "input"))
    )
    (net (code "63") (name "/~{IRQ}") (class "Default")
      (node (ref "IC19") (pin "4") (pinfunction "~{IRQ}_4") (pintype "input"))
      (node (ref "X1") (pin "4") (pinfunction "~{IRQ}_4") (pintype "open_collector"))
    )
    (net (code "64") (name "/~{LATCH_DATA_FROM_64}") (class "Default")
      (node (ref "IC15") (pin "15") (pinfunction "O3_15") (pintype "output"))
      (node (ref "IC6") (pin "1") (pinfunction "OC_1") (pintype "input"))
    )
    (net (code "65") (name "/~{NMI}") (class "Default")
      (node (ref "IC19") (pin "6") (pinfunction "~{NMI}_6") (pintype "input"))
      (node (ref "X1") (pin "D") (pinfunction "~{NMI}_D") (pintype "open_collector"))
    )
    (net (code "66") (name "/~{OE_ROM}") (class "Default")
      (node (ref "IC18") (pin "22") (pinfunction "~{OE}_22") (pintype "input"))
      (node (ref "U4") (pin "14") (pinfunction "O2_14") (pintype "bidirectional"))
    )
    (net (code "67") (name "/~{RDY}") (class "Default")
      (node (ref "IC14") (pin "19") (pinfunction "O7_19") (pintype "bidirectional"))
      (node (ref "IC19") (pin "2") (pinfunction "~{RDY}_2") (pintype "input"))
      (node (ref "U1") (pin "17") (pinfunction "O5_17") (pintype "bidirectional"))
    )
    (net (code "68") (name "/~{RESET}") (class "Default")
      (node (ref "IC19") (pin "40") (pinfunction "~{RESET}_40") (pintype "input"))
      (node (ref "IC9") (pin "13") (pinfunction "CLR_13") (pintype "input"))
      (node (ref "S2") (pin "2") (pinfunction "S_2") (pintype "passive"))
      (node (ref "U1") (pin "4") (pinfunction "I3_4") (pintype "input"))
      (node (ref "X1") (pin "C") (pinfunction "~{RESET}_C") (pintype "open_collector"))
    )
    (net (code "69") (name "/~{SO}") (class "Default")
      (node (ref "IC19") (pin "38") (pinfunction "~{SO}_38") (pintype "input"))
      (node (ref "U1") (pin "16") (pinfunction "O4_16") (pintype "bidirectional"))
    )
    (net (code "70") (name "/~{WE_RAM1}") (class "Default")
      (node (ref "IC10") (pin "8") (pinfunction "O_8") (pintype "output"))
      (node (ref "IC16") (pin "27") (pinfunction "~{WE}_27") (pintype "input"))
    )
    (net (code "71") (name "/~{WE_RAM2}") (class "Default")
      (node (ref "IC10") (pin "11") (pinfunction "O_11") (pintype "output"))
      (node (ref "IC17") (pin "27") (pinfunction "~{WE}_27") (pintype "input"))
    )
    (net (code "72") (name "/~{WR_DXXX}") (class "Default")
      (node (ref "IC15") (pin "7") (pinfunction "I5_7") (pintype "input"))
      (node (ref "U4") (pin "16") (pinfunction "O4_16") (pintype "bidirectional"))
    )
    (net (code "73") (name "64BA") (class "Default")
      (node (ref "IC11") (pin "11") (pinfunction "A1_11") (pintype "input"))
      (node (ref "X1") (pin "12") (pinfunction "BA_12") (pintype "bidirectional"))
    )
    (net (code "74") (name "64DMA") (class "Default")
      (node (ref "IC11") (pin "12") (pinfunction "Y4_12") (pintype "tri_state"))
      (node (ref "X1") (pin "13") (pinfunction "DMA_13") (pintype "bidirectional"))
    )
    (net (code "75") (name "64PHI2") (class "Default")
      (node (ref "IC11") (pin "15") (pinfunction "A3_15") (pintype "input"))
      (node (ref "X1") (pin "E") (pinfunction "PHI2_E") (pintype "output"))
    )
    (net (code "76") (name "A13_ROM") (class "Default")
      (node (ref "IC18") (pin "26") (pinfunction "A13_26") (pintype "input"))
      (node (ref "U1") (pin "18") (pinfunction "O6_18") (pintype "bidirectional"))
    )
    (net (code "77") (name "A14_ROM") (class "Default")
      (node (ref "IC18") (pin "27") (pinfunction "A14_27") (pintype "input"))
      (node (ref "U1") (pin "19") (pinfunction "O7_19") (pintype "output"))
    )
    (net (code "78") (name "B64BA") (class "Default")
      (node (ref "IC11") (pin "9") (pinfunction "Y1_9") (pintype "tri_state"))
      (node (ref "IC14") (pin "3") (pinfunction "I1_3") (pintype "input"))
      (node (ref "IC15") (pin "2") (pinfunction "I0_2") (pintype "input"))
    )
    (net (code "79") (name "B64PHI2") (class "Default")
      (node (ref "IC11") (pin "5") (pinfunction "Y3_5") (pintype "tri_state"))
      (node (ref "IC14") (pin "1") (pinfunction "CLK_1") (pintype "input"))
      (node (ref "IC14") (pin "2") (pinfunction "I0_2") (pintype "input"))
      (node (ref "IC15") (pin "5") (pinfunction "I3_5") (pintype "input"))
      (node (ref "IC9") (pin "3") (pinfunction "CLK_3") (pintype "input"))
    )
    (net (code "80") (name "CLK_WR_0000") (class "Default")
      (node (ref "IC9") (pin "11") (pinfunction "CLK_11") (pintype "input"))
      (node (ref "U1") (pin "12") (pinfunction "O0_12") (pintype "output"))
    )
    (net (code "81") (name "CLK_WR_0001") (class "Default")
      (node (ref "IC8") (pin "11") (pinfunction "CLK_11") (pintype "input"))
      (node (ref "U1") (pin "14") (pinfunction "O2_14") (pintype "bidirectional"))
    )
    (net (code "82") (name "D7") (class "Default")
      (node (ref "IC16") (pin "19") (pinfunction "D7_19") (pintype "bidirectional"))
      (node (ref "IC17") (pin "19") (pinfunction "D7_19") (pintype "bidirectional"))
      (node (ref "IC18") (pin "19") (pinfunction "I/O7_19") (pintype "tri_state"))
      (node (ref "IC19") (pin "26") (pinfunction "D7_26") (pintype "bidirectional"))
      (node (ref "IC5") (pin "3") (pinfunction "1D_3") (pintype "input"))
      (node (ref "IC6") (pin "19") (pinfunction "8Q_19") (pintype "tri_state"))
      (node (ref "IC9") (pin "12") (pinfunction "D_12") (pintype "input"))
    )
    (net (code "83") (name "DISABLE") (class "Default")
      (node (ref "IC11") (pin "1") (pinfunction "G_1") (pintype "input"))
      (node (ref "R5") (pin "1") (pinfunction "1_1") (pintype "passive"))
      (node (ref "S1") (pin "8") (pinfunction "S_8") (pintype "passive"))
      (node (ref "U1") (pin "8") (pinfunction "I7_8") (pintype "input"))
    )
    (net (code "84") (name "DOTCLK") (class "Default")
      (node (ref "IC15") (pin "1") (pinfunction "CLK_1") (pintype "input"))
      (node (ref "X1") (pin "6") (pinfunction "DOTCLK_6") (pintype "output"))
    )
    (net (code "85") (name "DRV_64ADDR_HI") (class "Default")
      (node (ref "IC1") (pin "1") (pinfunction "G_1") (pintype "input"))
      (node (ref "IC1") (pin "19") (pinfunction "G_19") (pintype "input"))
      (node (ref "IC14") (pin "18") (pinfunction "O6_18") (pintype "bidirectional"))
      (node (ref "IC2") (pin "1") (pinfunction "G_1") (pintype "input"))
      (node (ref "IC2") (pin "19") (pinfunction "G_19") (pintype "input"))
    )
    (net (code "86") (name "GND") (class "Default")
      (node (ref "C1") (pin "2") (pinfunction "2_2") (pintype "passive"))
      (node (ref "C10") (pin "2") (pinfunction "2_2") (pintype "passive"))
      (node (ref "C11") (pin "2") (pinfunction "2_2") (pintype "passive"))
      (node (ref "C2") (pin "2") (pinfunction "2_2") (pintype "passive"))
      (node (ref "C3") (pin "2") (pinfunction "2_2") (pintype "passive"))
      (node (ref "C4") (pin "2") (pinfunction "2_2") (pintype "passive"))
      (node (ref "C5") (pin "2") (pinfunction "2_2") (pintype "passive"))
      (node (ref "C6") (pin "2") (pinfunction "2_2") (pintype "passive"))
      (node (ref "C7") (pin "2") (pinfunction "2_2") (pintype "passive"))
      (node (ref "C8") (pin "2") (pinfunction "2_2") (pintype "passive"))
      (node (ref "C9") (pin "2") (pinfunction "2_2") (pintype "passive"))
      (node (ref "IC11") (pin "19") (pinfunction "G_19") (pintype "input"))
      (node (ref "IC11") (pin "8") (pinfunction "A4_8") (pintype "input"))
      (node (ref "IC15") (pin "11") (pinfunction "OE_11") (pintype "input"))
      (node (ref "IC16") (pin "20") (pinfunction "~{CE}_20") (pintype "input"))
      (node (ref "IC17") (pin "20") (pinfunction "~{CE}_20") (pintype "input"))
      (node (ref "IC18") (pin "14") (pinfunction "VSS_14") (pintype "power_in"))
      (node (ref "IC18") (pin "20") (pinfunction "~{CE}_20") (pintype "input"))
      (node (ref "IC7") (pin "12") (pinfunction "Q4_12") (pintype "input"))
      (node (ref "IC7") (pin "14") (pinfunction "Q5_14") (pintype "input"))
      (node (ref "IC7") (pin "16") (pinfunction "Q6_16") (pintype "input"))
      (node (ref "IC7") (pin "18") (pinfunction "Q7_18") (pintype "input"))
      (node (ref "IC7") (pin "3") (pinfunction "Q0_3") (pintype "input"))
      (node (ref "IC7") (pin "5") (pinfunction "Q1_5") (pintype "input"))
      (node (ref "IC7") (pin "7") (pinfunction "Q2_7") (pintype "input"))
      (node (ref "IC7") (pin "9") (pinfunction "Q3_9") (pintype "input"))
      (node (ref "S1") (pin "14") (pinfunction "S_14") (pintype "passive"))
      (node (ref "S1") (pin "5") (pinfunction "O_5") (pintype "passive"))
      (node (ref "S1") (pin "6") (pinfunction "P_6") (pintype "passive"))
      (node (ref "S2") (pin "1") (pinfunction "P_1") (pintype "passive"))
    )
    (net (code "87") (name "IC15O0") (class "Default")
      (node (ref "IC15") (pin "12") (pinfunction "O0_12") (pintype "bidirectional"))
      (node (ref "IC9") (pin "4") (pinfunction "PRE_4") (pintype "input"))
    )
    (net (code "88") (name "IC15O4") (class "Default")
      (node (ref "IC14") (pin "5") (pinfunction "I3_5") (pintype "input"))
      (node (ref "IC15") (pin "16") (pinfunction "O4_16") (pintype "output"))
      (node (ref "IC9") (pin "2") (pinfunction "D_2") (pintype "input"))
    )
    (net (code "89") (name "IC15O6") (class "Default")
      (node (ref "IC10") (pin "2") (pinfunction "I1_2") (pintype "input"))
      (node (ref "IC15") (pin "18") (pinfunction "O6_18") (pintype "output"))
    )
    (net (code "90") (name "LATCH_TO_64") (class "Default")
      (node (ref "IC15") (pin "19") (pinfunction "O7_19") (pintype "bidirectional"))
      (node (ref "IC3") (pin "11") (pinfunction "CLK_11") (pintype "input"))
      (node (ref "IC4") (pin "11") (pinfunction "CLK_11") (pintype "input"))
      (node (ref "IC5") (pin "11") (pinfunction "CLK_11") (pintype "input"))
    )
    (net (code "91") (name "N$90") (class "Default")
      (node (ref "IC14") (pin "11") (pinfunction "OE_11") (pintype "input"))
      (node (ref "IC14") (pin "12") (pinfunction "O0_12") (pintype "bidirectional"))
      (node (ref "IC14") (pin "7") (pinfunction "I5_7") (pintype "input"))
      (node (ref "IC14") (pin "8") (pinfunction "I6_8") (pintype "input"))
      (node (ref "IC14") (pin "9") (pinfunction "I7_9") (pintype "input"))
    )
    (net (code "92") (name "Net-(IC10A-O)") (class "Default")
      (node (ref "IC10") (pin "3") (pinfunction "O_3") (pintype "output"))
      (node (ref "IC10") (pin "5") (pinfunction "I1_5") (pintype "input"))
    )
    (net (code "93") (name "Net-(S1A-P)") (class "Default")
      (node (ref "R7") (pin "1") (pinfunction "1_1") (pintype "passive"))
      (node (ref "S1") (pin "13") (pinfunction "P_13") (pintype "passive"))
      (node (ref "S1") (pin "3") (pinfunction "O_3") (pintype "passive"))
    )
    (net (code "94") (name "PHI0") (class "Default")
      (node (ref "IC15") (pin "13") (pinfunction "O1_13") (pintype "output"))
      (node (ref "IC19") (pin "37") (pinfunction "PHI0_37") (pintype "input"))
      (node (ref "U1") (pin "3") (pinfunction "I2_3") (pintype "input"))
      (node (ref "U4") (pin "2") (pinfunction "I1_2") (pintype "input"))
    )
    (net (code "95") (name "ROM_SEL") (class "Default")
      (node (ref "R6") (pin "1") (pinfunction "1_1") (pintype "passive"))
      (node (ref "S1") (pin "9") (pinfunction "P_9") (pintype "passive"))
      (node (ref "U1") (pin "9") (pinfunction "I8_9") (pintype "input"))
    )
    (net (code "96") (name "VCC") (class "Default")
      (node (ref "C1") (pin "1") (pinfunction "1_1") (pintype "passive"))
      (node (ref "C10") (pin "1") (pinfunction "1_1") (pintype "passive"))
      (node (ref "C11") (pin "1") (pinfunction "1_1") (pintype "passive"))
      (node (ref "C2") (pin "1") (pinfunction "1_1") (pintype "passive"))
      (node (ref "C3") (pin "1") (pinfunction "1_1") (pintype "passive"))
      (node (ref "C4") (pin "1") (pinfunction "1_1") (pintype "passive"))
      (node (ref "C5") (pin "1") (pinfunction "1_1") (pintype "passive"))
      (node (ref "C6") (pin "1") (pinfunction "1_1") (pintype "passive"))
      (node (ref "C7") (pin "1") (pinfunction "1_1") (pintype "passive"))
      (node (ref "C8") (pin "1") (pinfunction "1_1") (pintype "passive"))
      (node (ref "C9") (pin "1") (pinfunction "1_1") (pintype "passive"))
      (node (ref "IC1") (pin "11") (pinfunction "A1_11") (pintype "input"))
      (node (ref "IC1") (pin "13") (pinfunction "A2_13") (pintype "input"))
      (node (ref "IC1") (pin "15") (pinfunction "A3_15") (pintype "input"))
      (node (ref "IC1") (pin "17") (pinfunction "A4_17") (pintype "input"))
      (node (ref "IC1") (pin "2") (pinfunction "A1_2") (pintype "input"))
      (node (ref "IC1") (pin "4") (pinfunction "A2_4") (pintype "input"))
      (node (ref "IC1") (pin "6") (pinfunction "A3_6") (pintype "input"))
      (node (ref "IC1") (pin "8") (pinfunction "A4_8") (pintype "input"))
      (node (ref "IC14") (pin "4") (pinfunction "I2_4") (pintype "input"))
      (node (ref "IC14") (pin "6") (pinfunction "I4_6") (pintype "input"))
      (node (ref "IC18") (pin "28") (pinfunction "VCC_28") (pintype "power_in"))
      (node (ref "IC2") (pin "11") (pinfunction "A1_11") (pintype "input"))
      (node (ref "IC2") (pin "13") (pinfunction "A2_13") (pintype "input"))
      (node (ref "IC2") (pin "15") (pinfunction "A3_15") (pintype "input"))
      (node (ref "IC2") (pin "17") (pinfunction "A4_17") (pintype "input"))
      (node (ref "IC2") (pin "2") (pinfunction "A1_2") (pintype "input"))
      (node (ref "IC2") (pin "4") (pinfunction "A2_4") (pintype "input"))
      (node (ref "IC2") (pin "6") (pinfunction "A3_6") (pintype "input"))
      (node (ref "IC2") (pin "8") (pinfunction "A4_8") (pintype "input"))
      (node (ref "R1") (pin "2") (pinfunction "2_2") (pintype "passive"))
      (node (ref "R2") (pin "2") (pinfunction "2_2") (pintype "passive"))
      (node (ref "R3") (pin "2") (pinfunction "2_2") (pintype "passive"))
      (node (ref "R4") (pin "2") (pinfunction "2_2") (pintype "passive"))
      (node (ref "R5") (pin "2") (pinfunction "2_2") (pintype "passive"))
      (node (ref "R6") (pin "2") (pinfunction "2_2") (pintype "passive"))
      (node (ref "R7") (pin "2") (pinfunction "2_2") (pintype "passive"))
    )
    (net (code "97") (name "WEAK_HI") (class "Default")
      (node (ref "IC11") (pin "13") (pinfunction "A2_13") (pintype "input"))
      (node (ref "IC11") (pin "17") (pinfunction "A4_17") (pintype "input"))
      (node (ref "IC11") (pin "2") (pinfunction "A1_2") (pintype "input"))
      (node (ref "IC11") (pin "4") (pinfunction "A2_4") (pintype "input"))
      (node (ref "IC15") (pin "3") (pinfunction "I1_3") (pintype "input"))
      (node (ref "IC15") (pin "6") (pinfunction "I4_6") (pintype "input"))
      (node (ref "IC8") (pin "13") (pinfunction "5D_13") (pintype "input"))
      (node (ref "IC8") (pin "14") (pinfunction "6D_14") (pintype "input"))
      (node (ref "IC8") (pin "17") (pinfunction "7D_17") (pintype "input"))
      (node (ref "IC8") (pin "18") (pinfunction "8D_18") (pintype "input"))
      (node (ref "IC8") (pin "3") (pinfunction "1D_3") (pintype "input"))
      (node (ref "IC9") (pin "1") (pinfunction "CLR_1") (pintype "input"))
      (node (ref "IC9") (pin "10") (pinfunction "PRE_10") (pintype "input"))
      (node (ref "R1") (pin "1") (pinfunction "1_1") (pintype "passive"))
    )
    (net (code "98") (name "unconnected-(IC8A-1Q-Pad2)") (class "Default")
      (node (ref "IC8") (pin "2") (pinfunction "1Q_2") (pintype "tri_state"))
    )
    (net (code "99") (name "unconnected-(IC8A-5Q-Pad12)") (class "Default")
      (node (ref "IC8") (pin "12") (pinfunction "5Q_12") (pintype "tri_state"))
    )
    (net (code "100") (name "unconnected-(IC8A-6Q-Pad15)") (class "Default")
      (node (ref "IC8") (pin "15") (pinfunction "6Q_15") (pintype "tri_state"))
    )
    (net (code "101") (name "unconnected-(IC8A-7Q-Pad16)") (class "Default")
      (node (ref "IC8") (pin "16") (pinfunction "7Q_16") (pintype "tri_state"))
    )
    (net (code "102") (name "unconnected-(IC8A-8Q-Pad19)") (class "Default")
      (node (ref "IC8") (pin "19") (pinfunction "8Q_19") (pintype "tri_state"))
    )
    (net (code "103") (name "unconnected-(IC9A-~{Q}-Pad6)") (class "Default")
      (node (ref "IC9") (pin "6") (pinfunction "~{Q}_6") (pintype "output"))
    )
    (net (code "104") (name "unconnected-(IC9B-~{Q}-Pad8)") (class "Default")
      (node (ref "IC9") (pin "8") (pinfunction "~{Q}_8") (pintype "output"))
    )
    (net (code "105") (name "unconnected-(IC11A-Y1-Pad18)") (class "Default")
      (node (ref "IC11") (pin "18") (pinfunction "Y1_18") (pintype "tri_state"))
    )
    (net (code "106") (name "unconnected-(IC11A-Y2-Pad16)") (class "Default")
      (node (ref "IC11") (pin "16") (pinfunction "Y2_16") (pintype "tri_state"))
    )
    (net (code "107") (name "unconnected-(IC11B-Y2-Pad7)") (class "Default")
      (node (ref "IC11") (pin "7") (pinfunction "Y2_7") (pintype "tri_state"))
    )
    (net (code "108") (name "unconnected-(IC11B-Y4-Pad3)") (class "Default")
      (node (ref "IC11") (pin "3") (pinfunction "Y4_3") (pintype "tri_state"))
    )
    (net (code "109") (name "unconnected-(IC14A-O1-Pad13)") (class "Default")
      (node (ref "IC14") (pin "13") (pinfunction "O1_13") (pintype "bidirectional"))
    )
    (net (code "110") (name "unconnected-(IC14A-O2-Pad14)") (class "Default")
      (node (ref "IC14") (pin "14") (pinfunction "O2_14") (pintype "output"))
    )
    (net (code "111") (name "unconnected-(IC14A-O3-Pad15)") (class "Default")
      (node (ref "IC14") (pin "15") (pinfunction "O3_15") (pintype "output"))
    )
    (net (code "112") (name "unconnected-(IC14A-O4-Pad16)") (class "Default")
      (node (ref "IC14") (pin "16") (pinfunction "O4_16") (pintype "output"))
    )
    (net (code "113") (name "unconnected-(IC14A-O5-Pad17)") (class "Default")
      (node (ref "IC14") (pin "17") (pinfunction "O5_17") (pintype "output"))
    )
    (net (code "114") (name "unconnected-(IC15A-O2-Pad14)") (class "Default")
      (node (ref "IC15") (pin "14") (pinfunction "O2_14") (pintype "output"))
    )
    (net (code "115") (name "unconnected-(IC15A-O5-Pad17)") (class "Default")
      (node (ref "IC15") (pin "17") (pinfunction "O5_17") (pintype "output"))
    )
    (net (code "116") (name "unconnected-(IC18-VPP-Pad1)") (class "Default")
      (node (ref "IC18") (pin "1") (pinfunction "VPP_1") (pintype "input"))
    )
    (net (code "117") (name "unconnected-(IC19A-PHI1-Pad3)") (class "Default")
      (node (ref "IC19") (pin "3") (pinfunction "PHI1_3") (pintype "output"))
    )
    (net (code "118") (name "unconnected-(IC19A-PHI2-Pad39)") (class "Default")
      (node (ref "IC19") (pin "39") (pinfunction "PHI2_39") (pintype "output"))
    )
    (net (code "119") (name "unconnected-(IC19A-SYNC-Pad7)") (class "Default")
      (node (ref "IC19") (pin "7") (pinfunction "SYNC_7") (pintype "output"))
    )
    (net (code "120") (name "unconnected-(S1A-O-Pad1)") (class "Default")
      (node (ref "S1") (pin "1") (pinfunction "O_1") (pintype "passive"))
    )
    (net (code "121") (name "unconnected-(S1C-S-Pad10)") (class "Default")
      (node (ref "S1") (pin "10") (pinfunction "S_10") (pintype "passive"))
    )
    (net (code "122") (name "unconnected-(S1D-O-Pad7)") (class "Default")
      (node (ref "S1") (pin "7") (pinfunction "O_7") (pintype "passive"))
    )
    (net (code "123") (name "unconnected-(U4A-O0-Pad12)") (class "Default")
      (node (ref "U4") (pin "12") (pinfunction "O0_12") (pintype "output"))
    )
    (net (code "124") (name "unconnected-(U4A-O1-Pad13)") (class "Default")
      (node (ref "U4") (pin "13") (pinfunction "O1_13") (pintype "bidirectional"))
    )
    (net (code "125") (name "unconnected-(X1A-~{EXROM}-Pad9)") (class "Default")
      (node (ref "X1") (pin "9") (pinfunction "~{EXROM}_9") (pintype "input"))
    )
    (net (code "126") (name "unconnected-(X1A-~{GAME}-Pad8)") (class "Default")
      (node (ref "X1") (pin "8") (pinfunction "~{GAME}_8") (pintype "input"))
    )
    (net (code "127") (name "unconnected-(X1A-~{IO1}-Pad7)") (class "Default")
      (node (ref "X1") (pin "7") (pinfunction "~{IO1}_7") (pintype "output"))
    )
    (net (code "128") (name "unconnected-(X1A-~{IO2}-Pad10)") (class "Default")
      (node (ref "X1") (pin "10") (pinfunction "~{IO2}_10") (pintype "output"))
    )
    (net (code "129") (name "unconnected-(X1A-~{ROMH}-PadB)") (class "Default")
      (node (ref "X1") (pin "B") (pinfunction "~{ROMH}_B") (pintype "output"))
    )
    (net (code "130") (name "unconnected-(X1A-~{ROML}-Pad11)") (class "Default")
      (node (ref "X1") (pin "11") (pinfunction "~{ROML}_11") (pintype "output"))
    )
  )
)
